# SC16IS750_Breakout.net
KiCad netlist of a schematic drawn in EAGLE
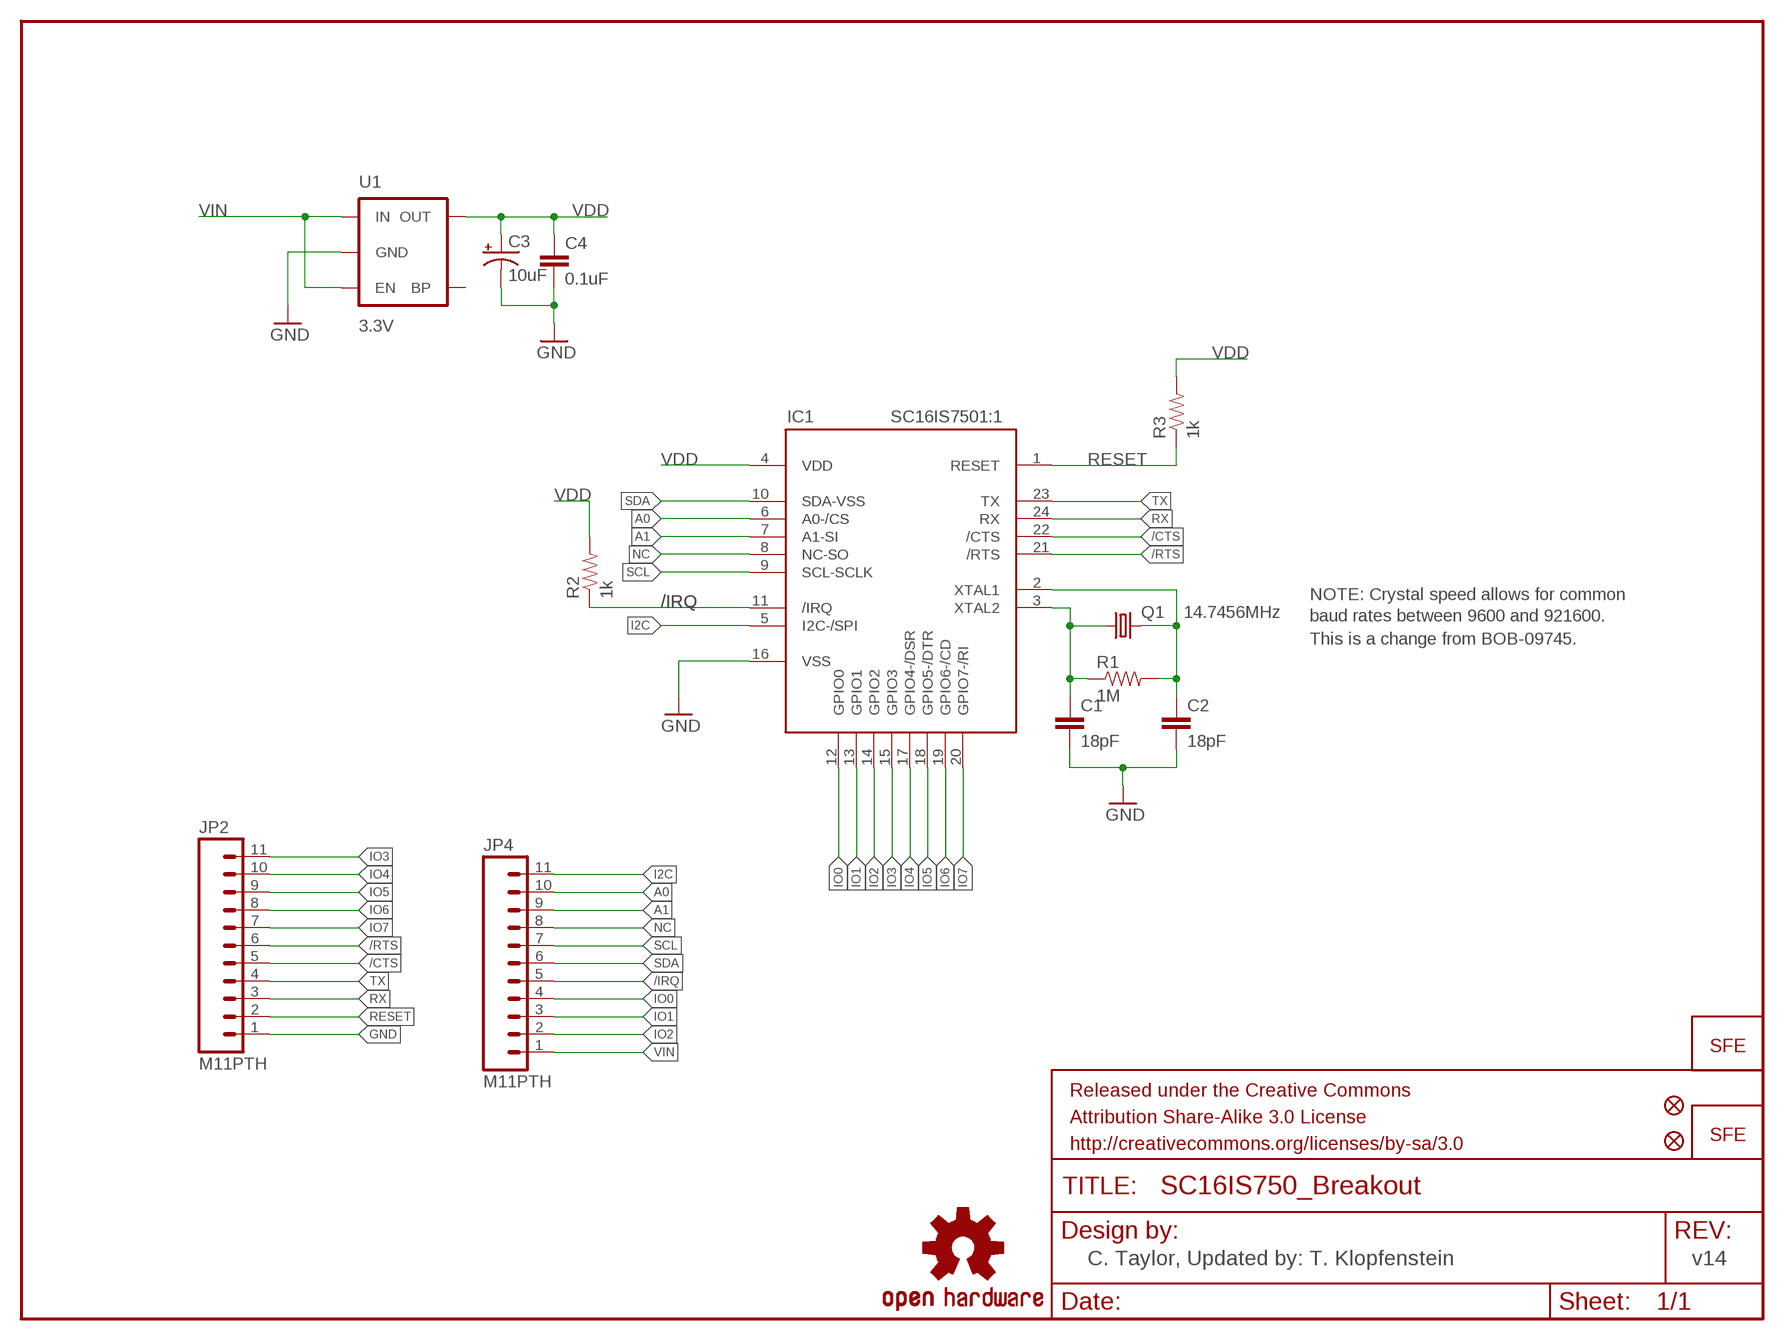
[diagram p0: schematic, sheet 1]

(export (version "E")
  (design (tool "Eeschema 10.0.6"))
  (components
    (comp (ref "C1")
      (value "18pF")
      (footprint "eagle-import:0603-CAP")
      (libsource (lib "eagle-import") (part "CAP0603-CAP"))
    )
    (comp (ref "C2")
      (value "18pF")
      (footprint "eagle-import:0603-CAP")
      (libsource (lib "eagle-import") (part "CAP0603-CAP"))
    )
    (comp (ref "C3")
      (value "10uF")
      (footprint "eagle-import:EIA3216")
      (libsource (lib "eagle-import") (part "CAP_POL1206"))
    )
    (comp (ref "C4")
      (value "0.1uF")
      (footprint "eagle-import:0603-CAP")
      (libsource (lib "eagle-import") (part "CAP0603-CAP"))
    )
    (comp (ref "IC1")
      (value "SC16IS7501:1")
      (footprint "eagle-import:QFN-24_1_1")
      (libsource (lib "eagle-import") (part "SC16IS7501{colon}1"))
    )
    (comp (ref "JP1")
      (value "LOGO-SFENEW")
      (footprint "eagle-import:SFE-NEW-WEBLOGO")
      (libsource (lib "eagle-import") (part "LOGO-SFENEW"))
    )
    (comp (ref "JP2")
      (value "M11PTH")
      (footprint "eagle-import:1X11")
      (libsource (lib "eagle-import") (part "M11PTH"))
    )
    (comp (ref "JP3")
      (value "LOGO-SFESK")
      (footprint "eagle-import:SFE-LOGO-FLAME")
      (libsource (lib "eagle-import") (part "LOGO-SFESK"))
    )
    (comp (ref "JP4")
      (value "M11PTH")
      (footprint "eagle-import:1X11")
      (libsource (lib "eagle-import") (part "M11PTH"))
    )
    (comp (ref "JP5")
      (value "FIDUCIAL1X2")
      (footprint "eagle-import:FIDUCIAL-1X2")
      (libsource (lib "eagle-import") (part "FIDUCIAL1X2"))
    )
    (comp (ref "JP6")
      (value "FIDUCIAL1X2")
      (footprint "eagle-import:FIDUCIAL-1X2")
      (libsource (lib "eagle-import") (part "FIDUCIAL1X2"))
    )
    (comp (ref "Q1")
      (value "14.7456MHz")
      (footprint "eagle-import:CRYSTAL-SMD-5X3")
      (libsource (lib "eagle-import") (part "CRYSTAL5X3"))
    )
    (comp (ref "R1")
      (value "1M")
      (footprint "eagle-import:0603-RES")
      (libsource (lib "eagle-import") (part "RESISTOR0603-RES"))
    )
    (comp (ref "R2")
      (value "1k")
      (footprint "eagle-import:0603-RES")
      (libsource (lib "eagle-import") (part "RESISTOR0603-RES"))
    )
    (comp (ref "R3")
      (value "1k")
      (footprint "eagle-import:0603-RES")
      (libsource (lib "eagle-import") (part "RESISTOR0603-RES"))
    )
    (comp (ref "U$1")
      (value "OSHW-LOGOS")
      (footprint "eagle-import:OSHW-LOGO-S")
      (libsource (lib "eagle-import") (part "OSHW-LOGOS"))
    )
    (comp (ref "U1")
      (value "3.3V")
      (footprint "eagle-import:SOT23-5")
      (libsource (lib "eagle-import") (part "V_REG_LDOSMD"))
    )
  )
  (nets
    (net (code "1") (name "/VDD") (class "Default")
      (node (ref "C3") (pin "A") (pinfunction "+_A") (pintype "passive"))
      (node (ref "C4") (pin "1") (pinfunction "1_1") (pintype "passive"))
      (node (ref "IC1") (pin "4") (pinfunction "VDD_4") (pintype "bidirectional"))
      (node (ref "R2") (pin "2") (pinfunction "2_2") (pintype "passive"))
      (node (ref "R3") (pin "2") (pinfunction "2_2") (pintype "passive"))
      (node (ref "U1") (pin "5") (pinfunction "OUT_5") (pintype "passive"))
    )
    (net (code "2") (name "A0") (class "Default")
      (node (ref "IC1") (pin "6") (pinfunction "A0-/CS_6") (pintype "bidirectional"))
      (node (ref "JP4") (pin "10") (pinfunction "10_10") (pintype "passive"))
    )
    (net (code "3") (name "A1") (class "Default")
      (node (ref "IC1") (pin "7") (pinfunction "A1-SI_7") (pintype "bidirectional"))
      (node (ref "JP4") (pin "9") (pinfunction "9_9") (pintype "passive"))
    )
    (net (code "4") (name "GND") (class "Default")
      (node (ref "C1") (pin "2") (pinfunction "2_2") (pintype "passive"))
      (node (ref "C2") (pin "2") (pinfunction "2_2") (pintype "passive"))
      (node (ref "C3") (pin "C") (pinfunction "-_C") (pintype "passive"))
      (node (ref "C4") (pin "2") (pinfunction "2_2") (pintype "passive"))
      (node (ref "IC1") (pin "16") (pinfunction "VSS_16") (pintype "bidirectional"))
      (node (ref "JP2") (pin "1") (pinfunction "1_1") (pintype "passive"))
      (node (ref "U1") (pin "2") (pinfunction "GND_2") (pintype "input"))
    )
    (net (code "5") (name "I2C") (class "Default")
      (node (ref "IC1") (pin "5") (pinfunction "I2C-/SPI_5") (pintype "bidirectional"))
      (node (ref "JP4") (pin "11") (pinfunction "11_11") (pintype "passive"))
    )
    (net (code "6") (name "IO0") (class "Default")
      (node (ref "IC1") (pin "12") (pinfunction "GPIO0_12") (pintype "bidirectional"))
      (node (ref "JP4") (pin "4") (pinfunction "4_4") (pintype "passive"))
    )
    (net (code "7") (name "IO1") (class "Default")
      (node (ref "IC1") (pin "13") (pinfunction "GPIO1_13") (pintype "bidirectional"))
      (node (ref "JP4") (pin "3") (pinfunction "3_3") (pintype "passive"))
    )
    (net (code "8") (name "IO2") (class "Default")
      (node (ref "IC1") (pin "14") (pinfunction "GPIO2_14") (pintype "bidirectional"))
      (node (ref "JP4") (pin "2") (pinfunction "2_2") (pintype "passive"))
    )
    (net (code "9") (name "IO3") (class "Default")
      (node (ref "IC1") (pin "15") (pinfunction "GPIO3_15") (pintype "bidirectional"))
      (node (ref "JP2") (pin "11") (pinfunction "11_11") (pintype "passive"))
    )
    (net (code "10") (name "IO4") (class "Default")
      (node (ref "IC1") (pin "17") (pinfunction "GPIO4-/DSR_17") (pintype "bidirectional"))
      (node (ref "JP2") (pin "10") (pinfunction "10_10") (pintype "passive"))
    )
    (net (code "11") (name "IO5") (class "Default")
      (node (ref "IC1") (pin "18") (pinfunction "GPIO5-/DTR_18") (pintype "bidirectional"))
      (node (ref "JP2") (pin "9") (pinfunction "9_9") (pintype "passive"))
    )
    (net (code "12") (name "IO6") (class "Default")
      (node (ref "IC1") (pin "19") (pinfunction "GPIO6-/CD_19") (pintype "bidirectional"))
      (node (ref "JP2") (pin "8") (pinfunction "8_8") (pintype "passive"))
    )
    (net (code "13") (name "IO7") (class "Default")
      (node (ref "IC1") (pin "20") (pinfunction "GPIO7-/RI_20") (pintype "bidirectional"))
      (node (ref "JP2") (pin "7") (pinfunction "7_7") (pintype "passive"))
    )
    (net (code "14") (name "NC") (class "Default")
      (node (ref "IC1") (pin "8") (pinfunction "NC-SO_8") (pintype "bidirectional"))
      (node (ref "JP4") (pin "8") (pinfunction "8_8") (pintype "passive"))
    )
    (net (code "15") (name "Net-(IC1-XTAL1)") (class "Default")
      (node (ref "C2") (pin "1") (pinfunction "1_1") (pintype "passive"))
      (node (ref "IC1") (pin "2") (pinfunction "XTAL1_2") (pintype "bidirectional"))
      (node (ref "Q1") (pin "3") (pinfunction "2_3") (pintype "passive"))
      (node (ref "R1") (pin "2") (pinfunction "2_2") (pintype "passive"))
    )
    (net (code "16") (name "Net-(IC1-XTAL2)") (class "Default")
      (node (ref "C1") (pin "1") (pinfunction "1_1") (pintype "passive"))
      (node (ref "IC1") (pin "3") (pinfunction "XTAL2_3") (pintype "bidirectional"))
      (node (ref "Q1") (pin "1") (pinfunction "1_1") (pintype "passive"))
      (node (ref "R1") (pin "1") (pinfunction "1_1") (pintype "passive"))
    )
    (net (code "17") (name "RESET") (class "Default")
      (node (ref "IC1") (pin "1") (pinfunction "RESET_1") (pintype "bidirectional"))
      (node (ref "JP2") (pin "2") (pinfunction "2_2") (pintype "passive"))
      (node (ref "R3") (pin "1") (pinfunction "1_1") (pintype "passive"))
    )
    (net (code "18") (name "RX") (class "Default")
      (node (ref "IC1") (pin "24") (pinfunction "RX_24") (pintype "bidirectional"))
      (node (ref "JP2") (pin "3") (pinfunction "3_3") (pintype "passive"))
    )
    (net (code "19") (name "SCL") (class "Default")
      (node (ref "IC1") (pin "9") (pinfunction "SCL-SCLK_9") (pintype "bidirectional"))
      (node (ref "JP4") (pin "7") (pinfunction "7_7") (pintype "passive"))
    )
    (net (code "20") (name "SDA") (class "Default")
      (node (ref "IC1") (pin "10") (pinfunction "SDA-VSS_10") (pintype "bidirectional"))
      (node (ref "JP4") (pin "6") (pinfunction "6_6") (pintype "passive"))
    )
    (net (code "21") (name "TX") (class "Default")
      (node (ref "IC1") (pin "23") (pinfunction "TX_23") (pintype "bidirectional"))
      (node (ref "JP2") (pin "4") (pinfunction "4_4") (pintype "passive"))
    )
    (net (code "22") (name "VIN") (class "Default")
      (node (ref "JP4") (pin "1") (pinfunction "1_1") (pintype "passive"))
      (node (ref "U1") (pin "1") (pinfunction "IN_1") (pintype "input"))
      (node (ref "U1") (pin "3") (pinfunction "EN_3") (pintype "input"))
    )
    (net (code "23") (name "unconnected-(U1-BP-Pad4)") (class "Default")
      (node (ref "U1") (pin "4") (pinfunction "BP_4") (pintype "input"))
    )
    (net (code "24") (name "{slash}CTS") (class "Default")
      (node (ref "IC1") (pin "22") (pinfunction "/CTS_22") (pintype "bidirectional"))
      (node (ref "JP2") (pin "5") (pinfunction "5_5") (pintype "passive"))
    )
    (net (code "25") (name "{slash}IRQ") (class "Default")
      (node (ref "IC1") (pin "11") (pinfunction "/IRQ_11") (pintype "bidirectional"))
      (node (ref "JP4") (pin "5") (pinfunction "5_5") (pintype "passive"))
      (node (ref "R2") (pin "1") (pinfunction "1_1") (pintype "passive"))
    )
    (net (code "26") (name "{slash}RTS") (class "Default")
      (node (ref "IC1") (pin "21") (pinfunction "/RTS_21") (pintype "bidirectional"))
      (node (ref "JP2") (pin "6") (pinfunction "6_6") (pintype "passive"))
    )
  )
)
